# trif_F.net
KiCad netlist of a schematic drawn in EAGLE
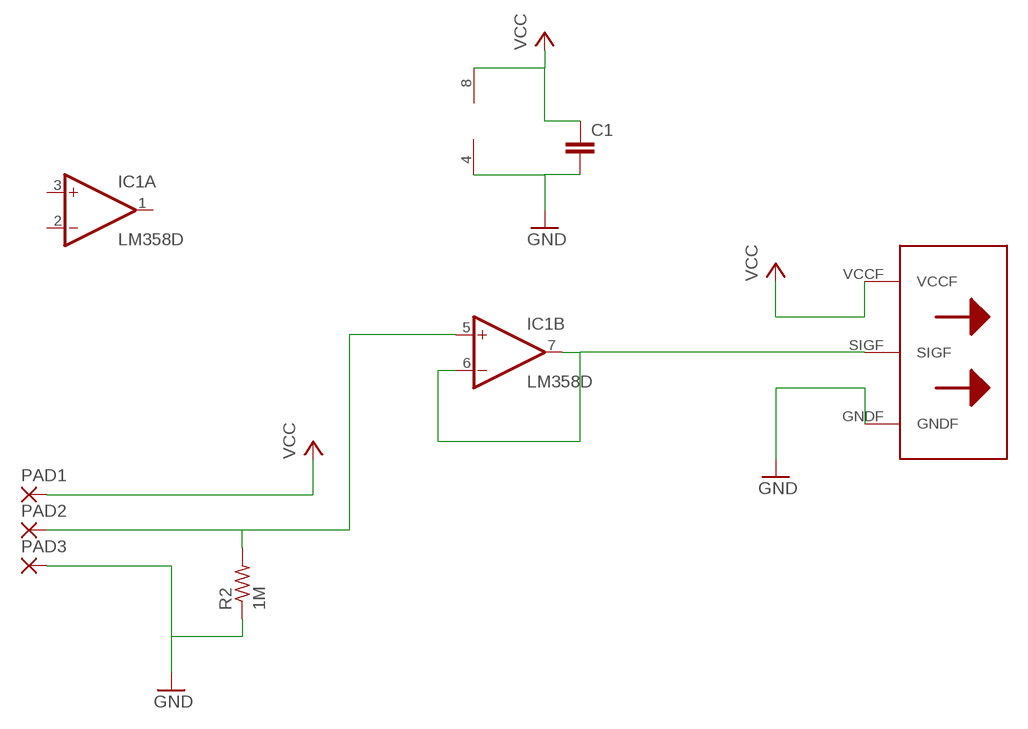
[diagram p0: schematic, sheet 1]

(export (version "E")
  (design (tool "Eeschema 10.0.6"))
  (components
    (comp (ref "C1")
      (value "C-EUC1206K")
      (footprint "eagle-import:C1206K")
      (libsource (lib "eagle-import") (part "C-EUC1206K"))
    )
    (comp (ref "IC1")
      (value "LM358D")
      (footprint "eagle-import:SO08")
      (libsource (lib "eagle-import") (part "LM358D"))
    )
    (comp (ref "PAD1")
      (value "SMD2")
      (footprint "eagle-import:SMD1,27-2,54")
      (libsource (lib "eagle-import") (part "SMD2"))
    )
    (comp (ref "PAD2")
      (value "SMD2")
      (footprint "eagle-import:SMD1,27-2,54")
      (libsource (lib "eagle-import") (part "SMD2"))
    )
    (comp (ref "PAD3")
      (value "SMD2")
      (footprint "eagle-import:SMD1,27-2,54")
      (libsource (lib "eagle-import") (part "SMD2"))
    )
    (comp (ref "R2")
      (value "1M")
      (footprint "eagle-import:M0805")
      (libsource (lib "eagle-import") (part "R-US_M0805"))
    )
    (comp (ref "U$2")
      (value "BITWIREF")
      (footprint "eagle-import:BITWIREF")
      (libsource (lib "eagle-import") (part "BITWIREF"))
    )
  )
  (nets
    (net (code "1") (name "GND") (class "Default")
      (node (ref "C1") (pin "2") (pinfunction "2_2") (pintype "passive"))
      (node (ref "IC1") (pin "4") (pinfunction "V-_4") (pintype "power_in"))
      (node (ref "PAD3") (pin "1") (pinfunction "P_1") (pintype "passive"))
      (node (ref "R2") (pin "1") (pinfunction "1_1") (pintype "passive"))
      (node (ref "U$2") (pin "GNDF") (pinfunction "GNDF_GNDF") (pintype "bidirectional"))
    )
    (net (code "2") (name "Net-(IC1B-+IN)") (class "Default")
      (node (ref "IC1") (pin "5") (pinfunction "+IN_5") (pintype "input"))
      (node (ref "PAD2") (pin "1") (pinfunction "P_1") (pintype "passive"))
      (node (ref "R2") (pin "2") (pinfunction "2_2") (pintype "passive"))
    )
    (net (code "3") (name "Net-(IC1B--IN)") (class "Default")
      (node (ref "IC1") (pin "6") (pinfunction "-IN_6") (pintype "input"))
      (node (ref "IC1") (pin "7") (pinfunction "OUT_7") (pintype "output"))
      (node (ref "U$2") (pin "SIGF") (pinfunction "SIGF_SIGF") (pintype "bidirectional"))
    )
    (net (code "4") (name "VCC") (class "Default")
      (node (ref "C1") (pin "1") (pinfunction "1_1") (pintype "passive"))
      (node (ref "IC1") (pin "8") (pinfunction "V+_8") (pintype "power_in"))
      (node (ref "PAD1") (pin "1") (pinfunction "P_1") (pintype "passive"))
      (node (ref "U$2") (pin "VCCF") (pinfunction "VCCF_VCCF") (pintype "bidirectional"))
    )
    (net (code "5") (name "unconnected-(IC1A-+IN-Pad3)") (class "Default")
      (node (ref "IC1") (pin "3") (pinfunction "+IN_3") (pintype "input"))
    )
    (net (code "6") (name "unconnected-(IC1A--IN-Pad2)") (class "Default")
      (node (ref "IC1") (pin "2") (pinfunction "-IN_2") (pintype "input"))
    )
    (net (code "7") (name "unconnected-(IC1A-OUT-Pad1)") (class "Default")
      (node (ref "IC1") (pin "1") (pinfunction "OUT_1") (pintype "output"))
    )
  )
)
